# d0reader.net
KiCad netlist of a schematic drawn in EAGLE
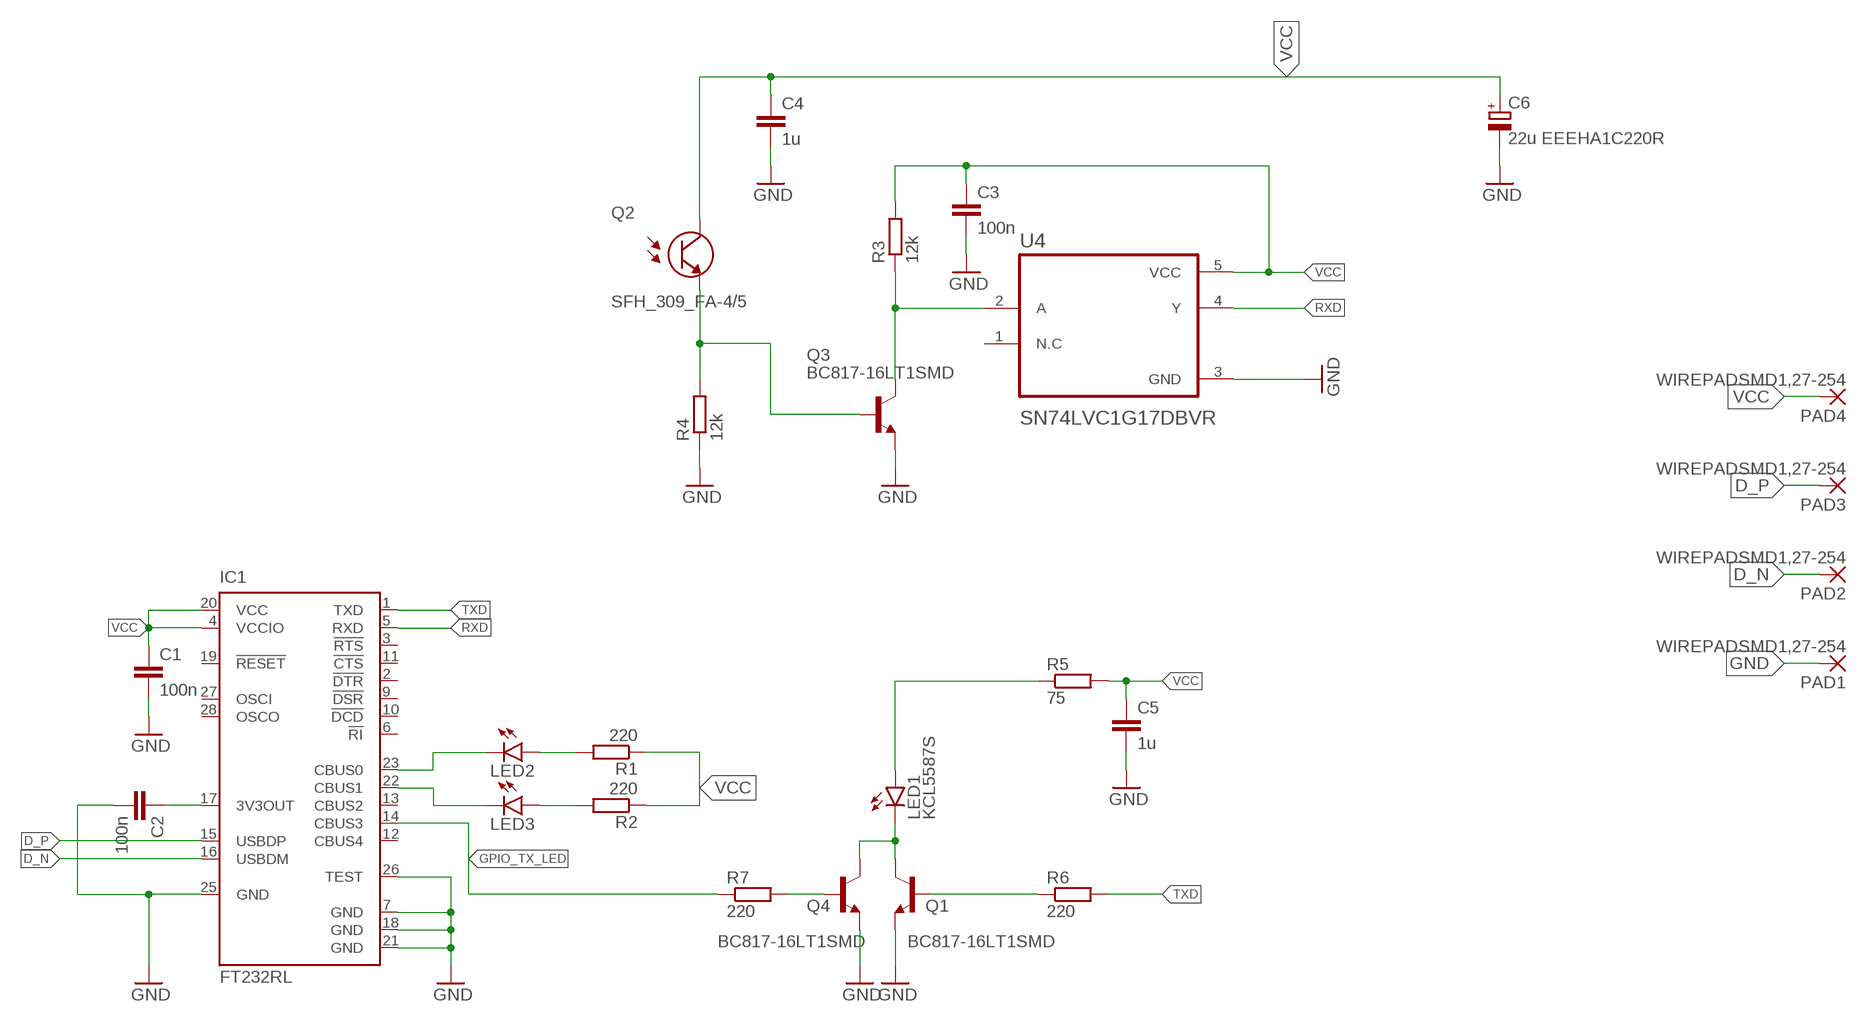
[diagram p0: schematic, sheet 1]

(export (version "E")
  (design (tool "Eeschema 10.0.6"))
  (components
    (comp (ref "C1")
      (value "100n")
      (footprint "eagle-import:C0805")
      (libsource (lib "eagle-import") (part "C-EUC0805"))
    )
    (comp (ref "C2")
      (value "100n")
      (footprint "eagle-import:C0805")
      (libsource (lib "eagle-import") (part "C-EUC0805"))
    )
    (comp (ref "C3")
      (value "100n")
      (footprint "eagle-import:C0805")
      (libsource (lib "eagle-import") (part "C-EUC0805"))
    )
    (comp (ref "C4")
      (value "1u")
      (footprint "eagle-import:C0805")
      (libsource (lib "eagle-import") (part "C-EUC0805"))
    )
    (comp (ref "C5")
      (value "1u")
      (footprint "eagle-import:C0805")
      (libsource (lib "eagle-import") (part "C-EUC0805"))
    )
    (comp (ref "C6")
      (value "22u EEEHA1C220R")
      (footprint "eagle-import:153CLV-0505")
      (libsource (lib "eagle-import") (part "CPOL-EU153CLV-0505"))
    )
    (comp (ref "IC1")
      (value "FT232RL")
      (footprint "eagle-import:SSOP28")
      (libsource (lib "eagle-import") (part "FT232RL"))
    )
    (comp (ref "LED1")
      (value "KCL5587S")
      (footprint "eagle-import:LED5MM")
      (libsource (lib "eagle-import") (part "LED5MM"))
    )
    (comp (ref "LED2")
      (value "LEDCHIPLED_0805")
      (footprint "eagle-import:CHIPLED_0805")
      (libsource (lib "eagle-import") (part "LEDCHIPLED_0805"))
    )
    (comp (ref "LED3")
      (value "LEDCHIPLED_0805")
      (footprint "eagle-import:CHIPLED_0805")
      (libsource (lib "eagle-import") (part "LEDCHIPLED_0805"))
    )
    (comp (ref "PAD1")
      (value "WIREPADSMD1,27-254")
      (footprint "eagle-import:SMD1,27-2,54")
      (libsource (lib "eagle-import") (part "WIREPADSMD1,27-254"))
    )
    (comp (ref "PAD2")
      (value "WIREPADSMD1,27-254")
      (footprint "eagle-import:SMD1,27-2,54")
      (libsource (lib "eagle-import") (part "WIREPADSMD1,27-254"))
    )
    (comp (ref "PAD3")
      (value "WIREPADSMD1,27-254")
      (footprint "eagle-import:SMD1,27-2,54")
      (libsource (lib "eagle-import") (part "WIREPADSMD1,27-254"))
    )
    (comp (ref "PAD4")
      (value "WIREPADSMD1,27-254")
      (footprint "eagle-import:SMD1,27-2,54")
      (libsource (lib "eagle-import") (part "WIREPADSMD1,27-254"))
    )
    (comp (ref "Q1")
      (value "BC817-16LT1SMD")
      (footprint "eagle-import:SOT23-BEC")
      (libsource (lib "eagle-import") (part "BC817SMD-16LT1"))
    )
    (comp (ref "Q2")
      (value "SFH_309_FA-4/5")
      (footprint "eagle-import:XDCR_SFH_309_FA-4_5")
      (fields (field (name "MF") "OSRAM Opto") (field (name "MP") "SFH 309 FA-4/5"))
      (libsource (lib "eagle-import") (part "SFH_309_FA-4/5"))
    )
    (comp (ref "Q3")
      (value "BC817-16LT1SMD")
      (footprint "eagle-import:SOT23-BEC")
      (libsource (lib "eagle-import") (part "BC817SMD-16LT1"))
    )
    (comp (ref "Q4")
      (value "BC817-16LT1SMD")
      (footprint "eagle-import:SOT23-BEC")
      (libsource (lib "eagle-import") (part "BC817SMD-16LT1"))
    )
    (comp (ref "R1")
      (value "220")
      (footprint "eagle-import:R0805")
      (libsource (lib "eagle-import") (part "R-EU_R0805"))
    )
    (comp (ref "R2")
      (value "220")
      (footprint "eagle-import:R0805")
      (libsource (lib "eagle-import") (part "R-EU_R0805"))
    )
    (comp (ref "R3")
      (value "12k")
      (footprint "eagle-import:R0805")
      (libsource (lib "eagle-import") (part "R-EU_R0805"))
    )
    (comp (ref "R4")
      (value "12k")
      (footprint "eagle-import:R0805")
      (libsource (lib "eagle-import") (part "R-EU_R0805"))
    )
    (comp (ref "R5")
      (value "75")
      (footprint "eagle-import:R0805")
      (libsource (lib "eagle-import") (part "R-EU_R0805"))
    )
    (comp (ref "R6")
      (value "220")
      (footprint "eagle-import:R0805")
      (libsource (lib "eagle-import") (part "R-EU_R0805"))
    )
    (comp (ref "R7")
      (value "220")
      (footprint "eagle-import:R0805")
      (libsource (lib "eagle-import") (part "R-EU_R0805"))
    )
    (comp (ref "U4")
      (value "SN74LVC1G17DBVR")
      (footprint "eagle-import:SOT95P280X145-5N")
      (fields (field (name "MF") "Texas Instruments"))
      (libsource (lib "eagle-import") (part "SN74LVC1G17DBVR"))
    )
  )
  (nets
    (net (code "1") (name "D_N") (class "Default")
      (node (ref "IC1") (pin "16") (pinfunction "USBDM_16") (pintype "bidirectional"))
      (node (ref "PAD2") (pin "1") (pinfunction "P_1") (pintype "passive"))
    )
    (net (code "2") (name "D_P") (class "Default")
      (node (ref "IC1") (pin "15") (pinfunction "USBDP_15") (pintype "bidirectional"))
      (node (ref "PAD3") (pin "1") (pinfunction "P_1") (pintype "passive"))
    )
    (net (code "3") (name "GND") (class "Default")
      (node (ref "C1") (pin "2") (pinfunction "2_2") (pintype "passive"))
      (node (ref "C2") (pin "2") (pinfunction "2_2") (pintype "passive"))
      (node (ref "C3") (pin "2") (pinfunction "2_2") (pintype "passive"))
      (node (ref "C4") (pin "2") (pinfunction "2_2") (pintype "passive"))
      (node (ref "C5") (pin "2") (pinfunction "2_2") (pintype "passive"))
      (node (ref "C6") (pin "-") (pinfunction "-_-") (pintype "passive"))
      (node (ref "IC1") (pin "18") (pinfunction "GND_18") (pintype "power_in"))
      (node (ref "IC1") (pin "21") (pinfunction "GND_21") (pintype "power_in"))
      (node (ref "IC1") (pin "25") (pinfunction "GND_25") (pintype "power_in"))
      (node (ref "IC1") (pin "26") (pinfunction "TEST_26") (pintype "input"))
      (node (ref "IC1") (pin "7") (pinfunction "GND_7") (pintype "power_in"))
      (node (ref "PAD1") (pin "1") (pinfunction "P_1") (pintype "passive"))
      (node (ref "Q1") (pin "E") (pinfunction "E_E") (pintype "passive"))
      (node (ref "Q3") (pin "E") (pinfunction "E_E") (pintype "passive"))
      (node (ref "Q4") (pin "E") (pinfunction "E_E") (pintype "passive"))
      (node (ref "R4") (pin "1") (pinfunction "1_1") (pintype "passive"))
      (node (ref "U4") (pin "3") (pinfunction "GND_3") (pintype "power_in"))
    )
    (net (code "4") (name "GPIO_TX_LED") (class "Default")
      (node (ref "IC1") (pin "14") (pinfunction "CBUS3_14") (pintype "bidirectional"))
      (node (ref "R7") (pin "1") (pinfunction "1_1") (pintype "passive"))
    )
    (net (code "5") (name "Net-(IC1-3V3OUT)") (class "Default")
      (node (ref "C2") (pin "1") (pinfunction "1_1") (pintype "passive"))
      (node (ref "IC1") (pin "17") (pinfunction "3V3OUT_17") (pintype "output"))
    )
    (net (code "6") (name "Net-(IC1-CBUS0)") (class "Default")
      (node (ref "IC1") (pin "23") (pinfunction "CBUS0_23") (pintype "bidirectional"))
      (node (ref "LED2") (pin "C") (pinfunction "C_C") (pintype "passive"))
    )
    (net (code "7") (name "Net-(IC1-CBUS1)") (class "Default")
      (node (ref "IC1") (pin "22") (pinfunction "CBUS1_22") (pintype "bidirectional"))
      (node (ref "LED3") (pin "C") (pinfunction "C_C") (pintype "passive"))
    )
    (net (code "8") (name "Net-(LED1-C)") (class "Default")
      (node (ref "LED1") (pin "K") (pinfunction "C_K") (pintype "passive"))
      (node (ref "Q1") (pin "C") (pinfunction "C_C") (pintype "passive"))
      (node (ref "Q4") (pin "C") (pinfunction "C_C") (pintype "passive"))
    )
    (net (code "9") (name "Net-(LED1-PadA)") (class "Default")
      (node (ref "LED1") (pin "A") (pinfunction "A_A") (pintype "passive"))
      (node (ref "R5") (pin "1") (pinfunction "1_1") (pintype "passive"))
    )
    (net (code "10") (name "Net-(LED2-PadA)") (class "Default")
      (node (ref "LED2") (pin "A") (pinfunction "A_A") (pintype "passive"))
      (node (ref "R1") (pin "2") (pinfunction "2_2") (pintype "passive"))
    )
    (net (code "11") (name "Net-(LED3-PadA)") (class "Default")
      (node (ref "LED3") (pin "A") (pinfunction "A_A") (pintype "passive"))
      (node (ref "R2") (pin "2") (pinfunction "2_2") (pintype "passive"))
    )
    (net (code "12") (name "Net-(Q1-PadB)") (class "Default")
      (node (ref "Q1") (pin "B") (pinfunction "B_B") (pintype "passive"))
      (node (ref "R6") (pin "1") (pinfunction "1_1") (pintype "passive"))
    )
    (net (code "13") (name "Net-(Q2-E)") (class "Default")
      (node (ref "Q2") (pin "1") (pinfunction "E_1") (pintype "passive"))
      (node (ref "Q3") (pin "B") (pinfunction "B_B") (pintype "passive"))
      (node (ref "R4") (pin "2") (pinfunction "2_2") (pintype "passive"))
    )
    (net (code "14") (name "Net-(Q4-PadB)") (class "Default")
      (node (ref "Q4") (pin "B") (pinfunction "B_B") (pintype "passive"))
      (node (ref "R7") (pin "2") (pinfunction "2_2") (pintype "passive"))
    )
    (net (code "15") (name "Net-(U4-A)") (class "Default")
      (node (ref "Q3") (pin "C") (pinfunction "C_C") (pintype "passive"))
      (node (ref "R3") (pin "1") (pinfunction "1_1") (pintype "passive"))
      (node (ref "U4") (pin "2") (pinfunction "A_2") (pintype "input"))
    )
    (net (code "16") (name "RXD") (class "Default")
      (node (ref "IC1") (pin "5") (pinfunction "RXD_5") (pintype "input"))
      (node (ref "U4") (pin "4") (pinfunction "Y_4") (pintype "output"))
    )
    (net (code "17") (name "TXD") (class "Default")
      (node (ref "IC1") (pin "1") (pinfunction "TXD_1") (pintype "output"))
      (node (ref "R6") (pin "2") (pinfunction "2_2") (pintype "passive"))
    )
    (net (code "18") (name "VCC") (class "Default")
      (node (ref "C1") (pin "1") (pinfunction "1_1") (pintype "passive"))
      (node (ref "C3") (pin "1") (pinfunction "1_1") (pintype "passive"))
      (node (ref "C4") (pin "1") (pinfunction "1_1") (pintype "passive"))
      (node (ref "C5") (pin "1") (pinfunction "1_1") (pintype "passive"))
      (node (ref "C6") (pin "+") (pinfunction "+_+") (pintype "passive"))
      (node (ref "IC1") (pin "20") (pinfunction "VCC_20") (pintype "power_in"))
      (node (ref "IC1") (pin "4") (pinfunction "VCCIO_4") (pintype "power_in"))
      (node (ref "PAD4") (pin "1") (pinfunction "P_1") (pintype "passive"))
      (node (ref "Q2") (pin "2") (pinfunction "C_2") (pintype "passive"))
      (node (ref "R1") (pin "1") (pinfunction "1_1") (pintype "passive"))
      (node (ref "R2") (pin "1") (pinfunction "1_1") (pintype "passive"))
      (node (ref "R3") (pin "2") (pinfunction "2_2") (pintype "passive"))
      (node (ref "R5") (pin "2") (pinfunction "2_2") (pintype "passive"))
      (node (ref "U4") (pin "5") (pinfunction "VCC_5") (pintype "power_in"))
    )
    (net (code "19") (name "unconnected-(IC1-CBUS2-Pad13)") (class "Default")
      (node (ref "IC1") (pin "13") (pinfunction "CBUS2_13") (pintype "bidirectional"))
    )
    (net (code "20") (name "unconnected-(IC1-CBUS4-Pad12)") (class "Default")
      (node (ref "IC1") (pin "12") (pinfunction "CBUS4_12") (pintype "bidirectional"))
    )
    (net (code "21") (name "unconnected-(IC1-OSCI-Pad27)") (class "Default")
      (node (ref "IC1") (pin "27") (pinfunction "OSCI_27") (pintype "input"))
    )
    (net (code "22") (name "unconnected-(IC1-OSCO-Pad28)") (class "Default")
      (node (ref "IC1") (pin "28") (pinfunction "OSCO_28") (pintype "output"))
    )
    (net (code "23") (name "unconnected-(IC1-~{CTS}-Pad11)") (class "Default")
      (node (ref "IC1") (pin "11") (pinfunction "~{CTS}_11") (pintype "input"))
    )
    (net (code "24") (name "unconnected-(IC1-~{DCD}-Pad10)") (class "Default")
      (node (ref "IC1") (pin "10") (pinfunction "~{DCD}_10") (pintype "input"))
    )
    (net (code "25") (name "unconnected-(IC1-~{DSR}-Pad9)") (class "Default")
      (node (ref "IC1") (pin "9") (pinfunction "~{DSR}_9") (pintype "input"))
    )
    (net (code "26") (name "unconnected-(IC1-~{DTR}-Pad2)") (class "Default")
      (node (ref "IC1") (pin "2") (pinfunction "~{DTR}_2") (pintype "output"))
    )
    (net (code "27") (name "unconnected-(IC1-~{RESET}-Pad19)") (class "Default")
      (node (ref "IC1") (pin "19") (pinfunction "~{RESET}_19") (pintype "input"))
    )
    (net (code "28") (name "unconnected-(IC1-~{RI}-Pad6)") (class "Default")
      (node (ref "IC1") (pin "6") (pinfunction "~{RI}_6") (pintype "input"))
    )
    (net (code "29") (name "unconnected-(IC1-~{RTS}-Pad3)") (class "Default")
      (node (ref "IC1") (pin "3") (pinfunction "~{RTS}_3") (pintype "output"))
    )
    (net (code "30") (name "unconnected-(U4-N.C-Pad1)") (class "Default")
      (node (ref "U4") (pin "1") (pinfunction "N.C_1") (pintype "bidirectional"))
    )
  )
)
